# MCU.net
KiCad netlist of a schematic drawn in Altium Designer
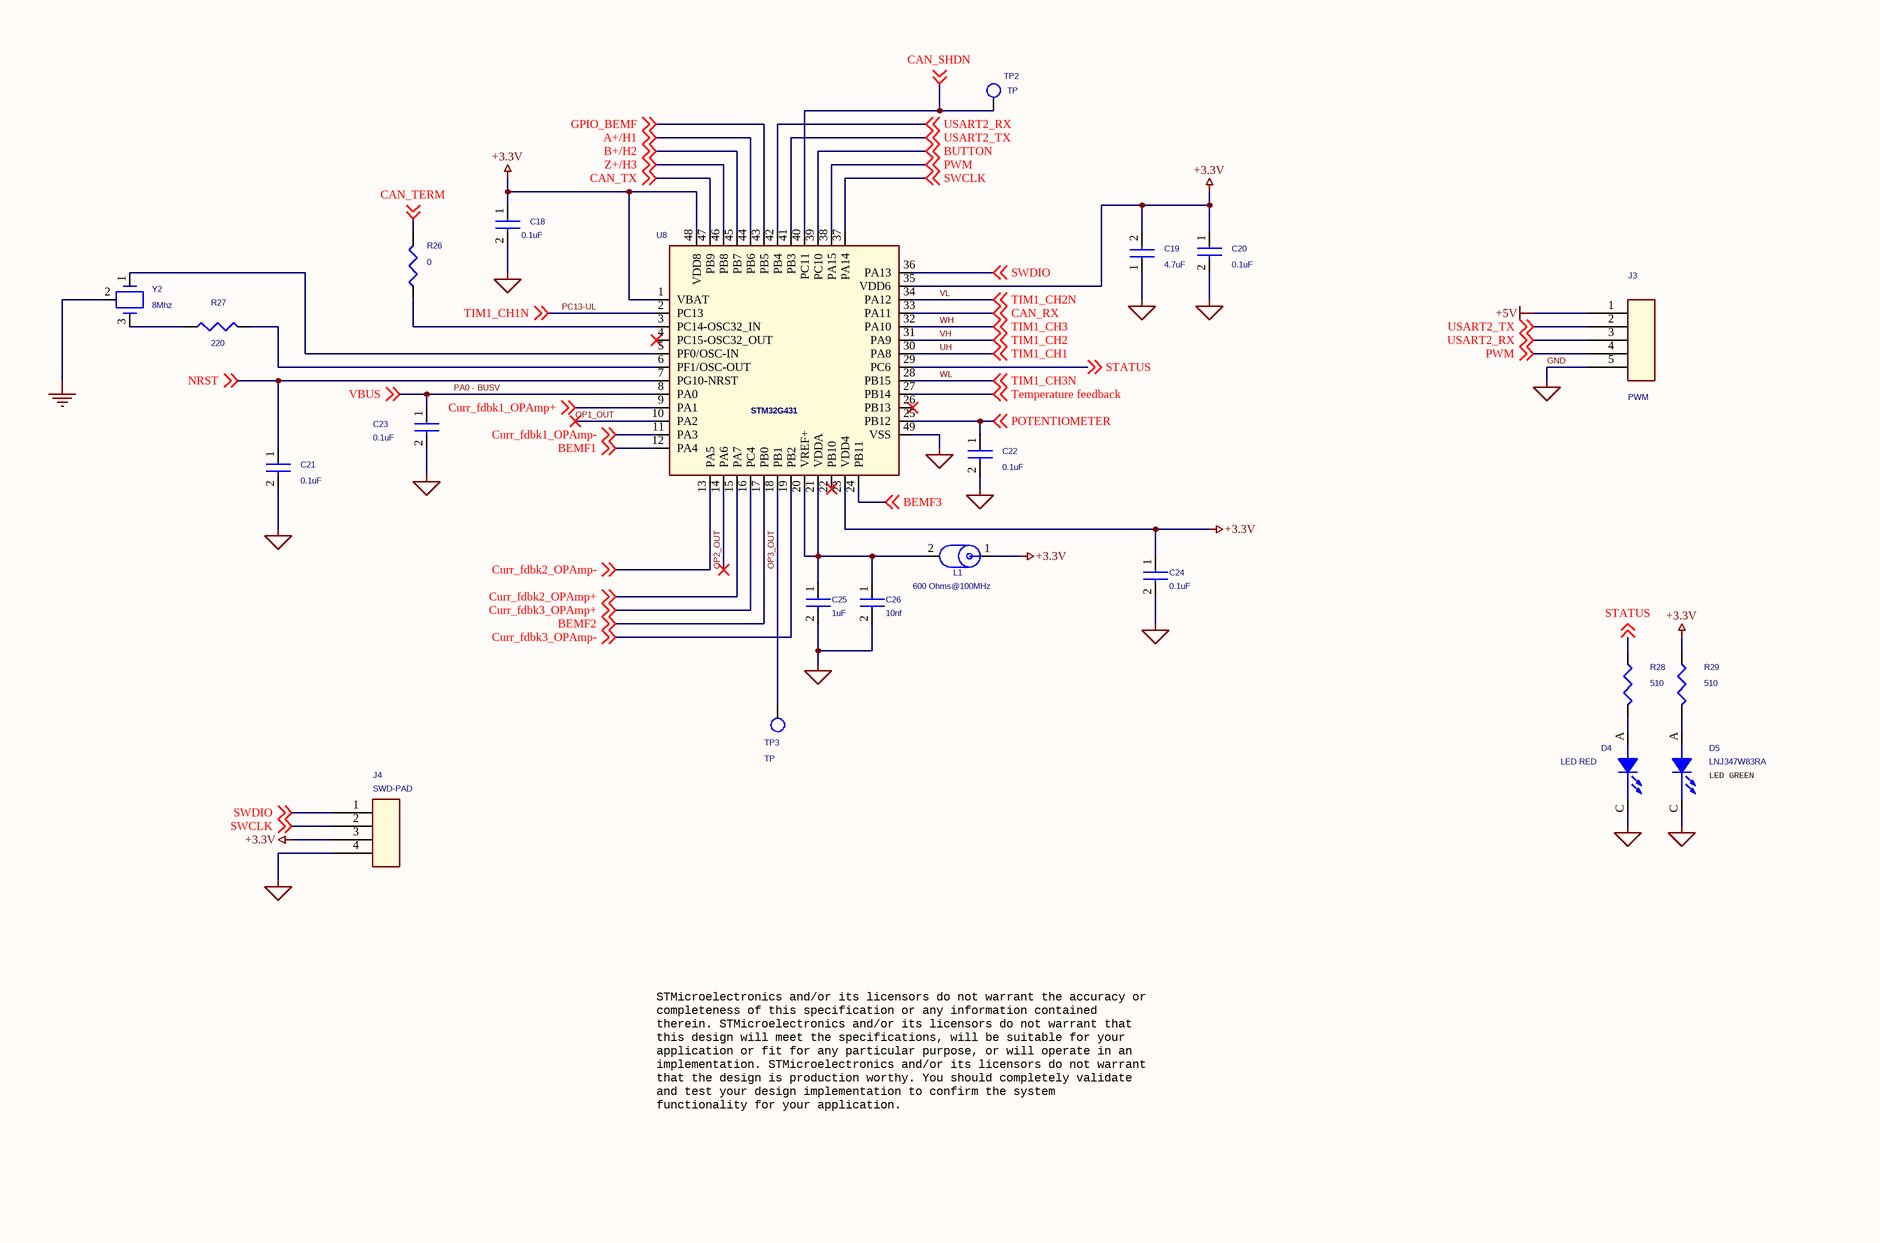
[diagram p0: MCU.SchDoc, top left]
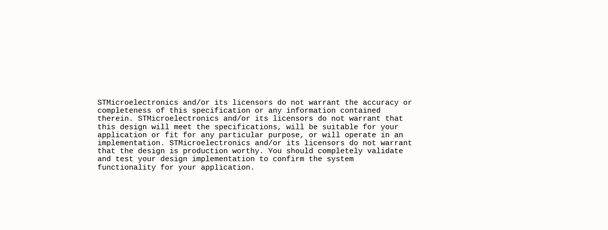
[diagram p1: MCU.SchDoc, bottom right]

(export (version "E")
  (design (tool "Eeschema 10.0.6"))
  (components
    (comp (ref "C18")
      (value "0.1uF")
      (footprint "C_0402")
      (description "CAP CER 0.1UF 16V X7R 0402")
      (fields (field (name "PART_NUMBER") "CAP-00000053") (field (name "TOLERANCE") "10%"))
      (libsource (lib "*") (part "CAP_Dup1"))
    )
    (comp (ref "C19")
      (value "4.7uF")
      (footprint "C_0603")
      (description "CAP CER 4.7UF 10V X5R 0603")
      (fields (field (name "MANUFACTURER") "Wurth Electronics Inc.") (field (name "TOLERANCE") "20%"))
      (libsource (lib "*") (part "CAP_Dup1"))
    )
    (comp (ref "C20")
      (value "0.1uF")
      (footprint "C_0402")
      (description "CAP CER 0.1UF 16V X7R 0402")
      (fields (field (name "MANUFACTURER") "Wurth Electronics Inc.") (field (name "TOLERANCE") "10%"))
      (libsource (lib "*") (part "CAP_Dup1"))
    )
    (comp (ref "C21")
      (value "0.1uF")
      (footprint "C_0402")
      (description "CAP CER 0.1UF 16V X7R 0402")
      (fields (field (name "MANUFACTURER") "Wurth Electronics Inc.") (field (name "TOLERANCE") "10%"))
      (libsource (lib "*") (part "CAP_Dup1"))
    )
    (comp (ref "C22")
      (value "0.1uF")
      (footprint "C_0402")
      (description "CAP CER 0.1UF 16V X7R 0402")
      (fields (field (name "PART_NUMBER") "CAP-00000053") (field (name "TOLERANCE") "10%"))
      (libsource (lib "*") (part "CAP_Dup1"))
    )
    (comp (ref "C23")
      (value "0.1uF")
      (footprint "C_0402")
      (description "CAP CER 0.1UF 16V X7R 0402")
      (fields (field (name "MANUFACTURER") "Wurth Electronics Inc.") (field (name "TOLERANCE") "10%"))
      (libsource (lib "*") (part "CAP_Dup1"))
    )
    (comp (ref "C24")
      (value "0.1uF")
      (footprint "C_0402")
      (description "CAP CER 0.1UF 16V X7R 0402")
      (fields (field (name "MANUFACTURER") "Wurth Electronics Inc.") (field (name "TOLERANCE") "10%"))
      (libsource (lib "*") (part "CAP_Dup1"))
    )
    (comp (ref "C25")
      (value "1uF")
      (footprint "C_0402")
      (description "CAP CER 1UF 25V X5R 0402")
      (fields (field (name "PART_NUMBER") "CAP-00000006") (field (name "TOLERANCE") "10%"))
      (libsource (lib "*") (part "CAP_Dup1"))
    )
    (comp (ref "C26")
      (value "10nf")
      (footprint "C_0402")
      (description "CAP CER 10000PF 16V X7R 0402")
      (fields (field (name "PART_NUMBER") "TMP-422") (field (name "TOLERANCE") "10%"))
      (libsource (lib "*") (part "CAP_Dup1"))
    )
    (comp (ref "D4")
      (value "LED RED")
      (footprint "D_0402_Led_red")
      (description "DIO, Rectangle with Flat Top, 1.00mm x 0.50mm, VLMS1500-GS08, 20mA, --, --, 0402 (1005 Metric)")
      (fields
        (field (name "PART_NUMBER") "DIO-00000003")
        (field (name "MANUFACTURER") "Vishay Semiconductor Opto Division")
      )
      (libsource (lib "*") (part "LED"))
    )
    (comp (ref "D5")
      (value "LNJ347W83RA")
      (footprint "D_0402_Led_green")
      (description "LED GREEN 0402 SMD")
      (fields
        (field (name "PART_NUMBER") "TMP-187")
        (field (name "MANUFACTURER") "Panasonic Electronic Components")
      )
      (libsource (lib "*") (part "LED"))
    )
    (comp (ref "J3")
      (value "PWM")
      (footprint "SOLDER_PAD_5PIN_SMD")
      (description "SOLDER PADS")
      (libsource (lib "*") (part "CON5"))
    )
    (comp (ref "J4")
      (value "SWD-PAD")
      (footprint "SOLDER_PAD_4PIN_rect_SMD")
      (description "SOLDER PADS")
      (libsource (lib "*") (part "CON4"))
    )
    (comp (ref "L1")
      (value "600 Ohms@100MHz")
      (footprint "L_0402")
      (description "FERRITE BEAD 600 OHM 0402 1LN")
      (fields
        (field (name "MANUFACTURER") "Murata Electronics North America")
        (field (name "PART_NUMBER") "TMP-492")
      )
      (libsource (lib "*") (part "IND_FB"))
    )
    (comp (ref "R26")
      (value "0")
      (footprint "R_0402")
      (description "RES SMD 0 OHM JUMPER 1/16W 0402")
      (fields (field (name "PART_NUMBER") "RES-00000073") (field (name "TOLERANCE") "Jumper"))
      (libsource (lib "*") (part "RES"))
    )
    (comp (ref "R27")
      (value "220")
      (footprint "R_0402")
      (description "RES SMD 220 OHM 1% 1/16W 0402")
      (fields (field (name "PART_NUMBER") "TMP-437") (field (name "TOLERANCE") "1%"))
      (libsource (lib "*") (part "RES"))
    )
    (comp (ref "R28")
      (value "510")
      (footprint "R_0402")
      (description "RES SMD 510 OHM 1% 1/16W 0402")
      (fields (field (name "PART_NUMBER") "TMP-438") (field (name "TOLERANCE") "1%"))
      (libsource (lib "*") (part "RES"))
    )
    (comp (ref "R29")
      (value "510")
      (footprint "R_0402")
      (description "RES SMD 510 OHM 1% 1/16W 0402")
      (fields (field (name "PART_NUMBER") "TMP-438") (field (name "TOLERANCE") "1%"))
      (libsource (lib "*") (part "RES"))
    )
    (comp (ref "TP2")
      (value "TP")
      (footprint "test_point_100_smd")
      (description "TEST POINT 1MM  SMD PADSTASCK")
      (fields (field (name "PART_NUMBER") "TMP-386"))
      (libsource (lib "*") (part "TESTPOINT"))
    )
    (comp (ref "TP3")
      (value "TP")
      (footprint "test_point_100_smd")
      (description "TEST POINT 1MM  SMD PADSTASCK")
      (fields (field (name "PART_NUMBER") "TMP-386"))
      (libsource (lib "*") (part "TESTPOINT"))
    )
    (comp (ref "U8")
      (value "STM32G431")
      (footprint "qfn49p50_700x700x60l40x25t560n")
      (libsource (lib "*") (part "STM32_LQFP64_6"))
    )
    (comp (ref "Y2")
      (value "8Mhz")
      (footprint "murata_cstce8m00g15c99-r0")
      (description "CER RES 8.0000MHZ 33PF SMD")
      (fields
        (field (name "MANUFACTURER") "Murata Electronics North America")
        (field (name "PART_NUMBER") "TMP-382")
      )
      (libsource (lib "*") (part "resonator"))
    )
  )
  (nets
    (net (code "1") (name "+3.3V") (class "Default")
      (node (ref "C18") (pin "1") (pinfunction "1_1") (pintype "passive"))
      (node (ref "C19") (pin "2") (pinfunction "2_2") (pintype "passive"))
      (node (ref "C20") (pin "1") (pinfunction "1_1") (pintype "passive"))
      (node (ref "C24") (pin "1") (pinfunction "1_1") (pintype "passive"))
      (node (ref "J4") (pin "3") (pinfunction "3_3") (pintype "passive"))
      (node (ref "L1") (pin "1") (pinfunction "1_1") (pintype "passive"))
      (node (ref "R29") (pin "1") (pinfunction "1_1") (pintype "passive"))
      (node (ref "U8") (pin "1") (pinfunction "VBAT_1") (pintype "passive"))
      (node (ref "U8") (pin "23") (pinfunction "VDD4_23") (pintype "passive"))
      (node (ref "U8") (pin "35") (pinfunction "VDD6_35") (pintype "passive"))
      (node (ref "U8") (pin "48") (pinfunction "VDD8_48") (pintype "passive"))
    )
    (net (code "2") (name "+5V") (class "Default")
      (node (ref "J3") (pin "1") (pinfunction "1_1") (pintype "passive"))
    )
    (net (code "3") (name "/OP1_OUT") (class "Default")
      (node (ref "U8") (pin "10") (pinfunction "PA2_10") (pintype "passive+no_connect"))
    )
    (net (code "4") (name "/OP2_OUT") (class "Default")
      (node (ref "U8") (pin "14") (pinfunction "PA6_14") (pintype "passive+no_connect"))
    )
    (net (code "5") (name "/OP3_OUT") (class "Default")
      (node (ref "TP3") (pin "1") (pinfunction "1_1") (pintype "passive"))
      (node (ref "U8") (pin "18") (pinfunction "PB1_18") (pintype "passive"))
    )
    (net (code "6") (name "A+{slash}H1") (class "Default")
      (node (ref "U8") (pin "44") (pinfunction "PB6_44") (pintype "passive"))
    )
    (net (code "7") (name "B+{slash}H2") (class "Default")
      (node (ref "U8") (pin "45") (pinfunction "PB7_45") (pintype "passive"))
    )
    (net (code "8") (name "BEMF1") (class "Default")
      (node (ref "U8") (pin "12") (pinfunction "PA4_12") (pintype "passive"))
    )
    (net (code "9") (name "BEMF2") (class "Default")
      (node (ref "U8") (pin "17") (pinfunction "PB0_17") (pintype "passive"))
    )
    (net (code "10") (name "BEMF3") (class "Default")
      (node (ref "U8") (pin "24") (pinfunction "PB11_24") (pintype "passive"))
    )
    (net (code "11") (name "BUTTON") (class "Default")
      (node (ref "U8") (pin "39") (pinfunction "PC10_39") (pintype "passive"))
    )
    (net (code "12") (name "CAN_RX") (class "Default")
      (node (ref "U8") (pin "33") (pinfunction "PA11_33") (pintype "passive"))
    )
    (net (code "13") (name "CAN_SHDN") (class "Default")
      (node (ref "TP2") (pin "1") (pinfunction "1_1") (pintype "passive"))
      (node (ref "U8") (pin "40") (pinfunction "PC11_40") (pintype "passive"))
    )
    (net (code "14") (name "CAN_TERM") (class "Default")
      (node (ref "R26") (pin "2") (pinfunction "2_2") (pintype "passive"))
    )
    (net (code "15") (name "CAN_TX") (class "Default")
      (node (ref "U8") (pin "47") (pinfunction "PB9_47") (pintype "passive"))
    )
    (net (code "16") (name "Curr_fdbk1_OPAmp+") (class "Default")
      (node (ref "U8") (pin "9") (pinfunction "PA1_9") (pintype "passive"))
    )
    (net (code "17") (name "Curr_fdbk1_OPAmp-") (class "Default")
      (node (ref "U8") (pin "11") (pinfunction "PA3_11") (pintype "passive"))
    )
    (net (code "18") (name "Curr_fdbk2_OPAmp+") (class "Default")
      (node (ref "U8") (pin "15") (pinfunction "PA7_15") (pintype "passive"))
    )
    (net (code "19") (name "Curr_fdbk2_OPAmp-") (class "Default")
      (node (ref "U8") (pin "13") (pinfunction "PA5_13") (pintype "passive"))
    )
    (net (code "20") (name "Curr_fdbk3_OPAmp+") (class "Default")
      (node (ref "U8") (pin "16") (pinfunction "PC4_16") (pintype "passive"))
    )
    (net (code "21") (name "Curr_fdbk3_OPAmp-") (class "Default")
      (node (ref "U8") (pin "19") (pinfunction "PB2_19") (pintype "passive"))
    )
    (net (code "22") (name "GND") (class "Default")
      (node (ref "C18") (pin "2") (pinfunction "2_2") (pintype "passive"))
      (node (ref "C19") (pin "1") (pinfunction "1_1") (pintype "passive"))
      (node (ref "C20") (pin "2") (pinfunction "2_2") (pintype "passive"))
      (node (ref "C21") (pin "2") (pinfunction "2_2") (pintype "passive"))
      (node (ref "C22") (pin "2") (pinfunction "2_2") (pintype "passive"))
      (node (ref "C23") (pin "2") (pinfunction "2_2") (pintype "passive"))
      (node (ref "C24") (pin "2") (pinfunction "2_2") (pintype "passive"))
      (node (ref "C25") (pin "2") (pinfunction "2_2") (pintype "passive"))
      (node (ref "C26") (pin "2") (pinfunction "2_2") (pintype "passive"))
      (node (ref "D4") (pin "C") (pinfunction "CATHODE_C") (pintype "passive"))
      (node (ref "D5") (pin "C") (pinfunction "CATHODE_C") (pintype "passive"))
      (node (ref "J3") (pin "5") (pinfunction "5_5") (pintype "passive"))
      (node (ref "J4") (pin "4") (pinfunction "4_4") (pintype "passive"))
      (node (ref "U8") (pin "49") (pinfunction "VSS_49") (pintype "passive"))
      (node (ref "Y2") (pin "2") (pinfunction "2_2") (pintype "passive"))
    )
    (net (code "23") (name "GPIO_BEMF") (class "Default")
      (node (ref "U8") (pin "43") (pinfunction "PB5_43") (pintype "passive"))
    )
    (net (code "24") (name "NRST") (class "Default")
      (node (ref "C21") (pin "1") (pinfunction "1_1") (pintype "passive"))
      (node (ref "U8") (pin "7") (pinfunction "PG10-NRST_7") (pintype "passive"))
    )
    (net (code "25") (name "Net-(D4-ANODE)") (class "Default")
      (node (ref "D4") (pin "A") (pinfunction "ANODE_A") (pintype "passive"))
      (node (ref "R28") (pin "2") (pinfunction "2_2") (pintype "passive"))
    )
    (net (code "26") (name "Net-(D5-ANODE)") (class "Default")
      (node (ref "D5") (pin "A") (pinfunction "ANODE_A") (pintype "passive"))
      (node (ref "R29") (pin "2") (pinfunction "2_2") (pintype "passive"))
    )
    (net (code "27") (name "Net-(R27-Pad1)") (class "Default")
      (node (ref "R27") (pin "1") (pinfunction "1_1") (pintype "passive"))
      (node (ref "Y2") (pin "3") (pinfunction "3_3") (pintype "passive"))
    )
    (net (code "28") (name "Net-(U8-PC14-OSC32_IN)") (class "Default")
      (node (ref "R26") (pin "1") (pinfunction "1_1") (pintype "passive"))
      (node (ref "U8") (pin "3") (pinfunction "PC14-OSC32_IN_3") (pintype "passive"))
    )
    (net (code "29") (name "Net-(U8-PF0{slash}OSC-IN)") (class "Default")
      (node (ref "U8") (pin "5") (pinfunction "PF0/OSC-IN_5") (pintype "passive"))
      (node (ref "Y2") (pin "1") (pinfunction "1_1") (pintype "passive"))
    )
    (net (code "30") (name "Net-(U8-PF1{slash}OSC-OUT)") (class "Default")
      (node (ref "R27") (pin "2") (pinfunction "2_2") (pintype "passive"))
      (node (ref "U8") (pin "6") (pinfunction "PF1/OSC-OUT_6") (pintype "passive"))
    )
    (net (code "31") (name "Net-(U8-VDDA)") (class "Default")
      (node (ref "C25") (pin "1") (pinfunction "1_1") (pintype "passive"))
      (node (ref "C26") (pin "1") (pinfunction "1_1") (pintype "passive"))
      (node (ref "L1") (pin "2") (pinfunction "2_2") (pintype "passive"))
      (node (ref "U8") (pin "20") (pinfunction "VREF+_20") (pintype "passive"))
      (node (ref "U8") (pin "21") (pinfunction "VDDA_21") (pintype "passive"))
    )
    (net (code "32") (name "POTENTIOMETER") (class "Default")
      (node (ref "C22") (pin "1") (pinfunction "1_1") (pintype "passive"))
      (node (ref "U8") (pin "25") (pinfunction "PB12_25") (pintype "passive"))
    )
    (net (code "33") (name "PWM") (class "Default")
      (node (ref "J3") (pin "4") (pinfunction "4_4") (pintype "passive"))
      (node (ref "U8") (pin "38") (pinfunction "PA15_38") (pintype "passive"))
    )
    (net (code "34") (name "STATUS") (class "Default")
      (node (ref "R28") (pin "1") (pinfunction "1_1") (pintype "passive"))
      (node (ref "U8") (pin "29") (pinfunction "PC6_29") (pintype "passive"))
    )
    (net (code "35") (name "SWCLK") (class "Default")
      (node (ref "J4") (pin "2") (pinfunction "2_2") (pintype "passive"))
      (node (ref "U8") (pin "37") (pinfunction "PA14_37") (pintype "passive"))
    )
    (net (code "36") (name "SWDIO") (class "Default")
      (node (ref "J4") (pin "1") (pinfunction "1_1") (pintype "passive"))
      (node (ref "U8") (pin "36") (pinfunction "PA13_36") (pintype "passive"))
    )
    (net (code "37") (name "TIM1_CH1") (class "Default")
      (node (ref "U8") (pin "30") (pinfunction "PA8_30") (pintype "passive"))
    )
    (net (code "38") (name "TIM1_CH1N") (class "Default")
      (node (ref "U8") (pin "2") (pinfunction "PC13_2") (pintype "passive"))
    )
    (net (code "39") (name "TIM1_CH2") (class "Default")
      (node (ref "U8") (pin "31") (pinfunction "PA9_31") (pintype "passive"))
    )
    (net (code "40") (name "TIM1_CH2N") (class "Default")
      (node (ref "U8") (pin "34") (pinfunction "PA12_34") (pintype "passive"))
    )
    (net (code "41") (name "TIM1_CH3") (class "Default")
      (node (ref "U8") (pin "32") (pinfunction "PA10_32") (pintype "passive"))
    )
    (net (code "42") (name "TIM1_CH3N") (class "Default")
      (node (ref "U8") (pin "28") (pinfunction "PB15_28") (pintype "passive"))
    )
    (net (code "43") (name "Temperature feedback") (class "Default")
      (node (ref "U8") (pin "27") (pinfunction "PB14_27") (pintype "passive"))
    )
    (net (code "44") (name "USART2_RX") (class "Default")
      (node (ref "J3") (pin "3") (pinfunction "3_3") (pintype "passive"))
      (node (ref "U8") (pin "42") (pinfunction "PB4_42") (pintype "passive"))
    )
    (net (code "45") (name "USART2_TX") (class "Default")
      (node (ref "J3") (pin "2") (pinfunction "2_2") (pintype "passive"))
      (node (ref "U8") (pin "41") (pinfunction "PB3_41") (pintype "passive"))
    )
    (net (code "46") (name "VBUS") (class "Default")
      (node (ref "C23") (pin "1") (pinfunction "1_1") (pintype "passive"))
      (node (ref "U8") (pin "8") (pinfunction "PA0_8") (pintype "passive"))
    )
    (net (code "47") (name "Z+{slash}H3") (class "Default")
      (node (ref "U8") (pin "46") (pinfunction "PB8_46") (pintype "passive"))
    )
    (net (code "48") (name "unconnected-(U8-PB10-Pad22)") (class "Default")
      (node (ref "U8") (pin "22") (pinfunction "PB10_22") (pintype "passive+no_connect"))
    )
    (net (code "49") (name "unconnected-(U8-PB13-Pad26)") (class "Default")
      (node (ref "U8") (pin "26") (pinfunction "PB13_26") (pintype "passive+no_connect"))
    )
    (net (code "50") (name "unconnected-(U8-PC15-OSC32_OUT-Pad4)") (class "Default")
      (node (ref "U8") (pin "4") (pinfunction "PC15-OSC32_OUT_4") (pintype "passive+no_connect"))
    )
  )
)
